# G-PiC_MotorShield.net
KiCad netlist of a schematic drawn in EAGLE
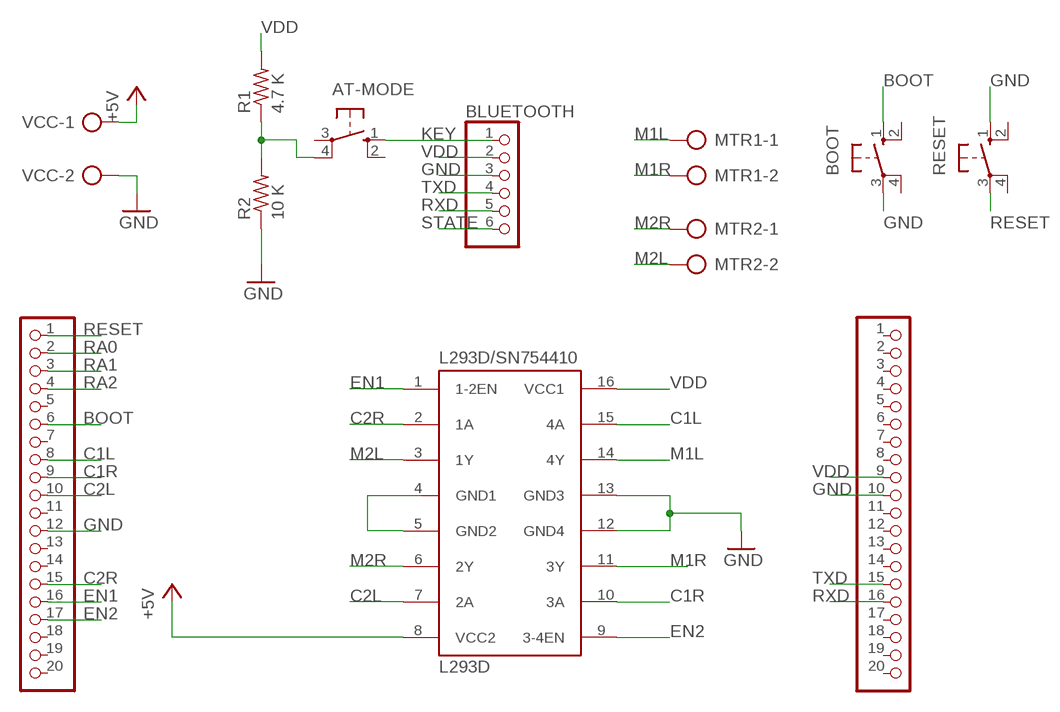
[diagram p0: schematic, sheet 1]

(export (version "E")
  (design (tool "Eeschema 10.0.6"))
  (components
    (comp (ref "AT-MODE")
      (value "10-XX")
      (footprint "eagle-import:B3F-10XX")
      (fields
        (field (name "MPN") "B3F-1000")
        (field (name "MPN_1") "B3F-1000")
        (field (name "OC_FARNELL") "176432")
        (field (name "OC_NEWARK") "36M3542")
      )
      (libsource (lib "eagle-import") (part "10-XX"))
    )
    (comp (ref "BLUETOOTH")
      (value "PINHD-1X6")
      (footprint "eagle-import:1X06")
      (libsource (lib "eagle-import") (part "PINHD-1X6"))
    )
    (comp (ref "BOOT")
      (value "10-XX")
      (footprint "eagle-import:B3F-10XX")
      (fields (field (name "MPN") "B3F-1000"))
      (libsource (lib "eagle-import") (part "10-XX"))
    )
    (comp (ref "JP1")
      (value "PINHD-1X20")
      (footprint "eagle-import:1X20")
      (libsource (lib "eagle-import") (part "PINHD-1X20"))
    )
    (comp (ref "JP2")
      (value "PINHD-1X20")
      (footprint "eagle-import:1X20")
      (libsource (lib "eagle-import") (part "PINHD-1X20"))
    )
    (comp (ref "L293D/SN754410")
      (value "L293D")
      (footprint "eagle-import:DIL16")
      (libsource (lib "eagle-import") (part "L293D"))
    )
    (comp (ref "MTR1")
      (value "AK300/2")
      (footprint "eagle-import:AK300_2")
      (libsource (lib "eagle-import") (part "AK300/2"))
    )
    (comp (ref "MTR2")
      (value "AK300/2")
      (footprint "eagle-import:AK300_2")
      (libsource (lib "eagle-import") (part "AK300/2"))
    )
    (comp (ref "R1")
      (value "4.7 K")
      (footprint "eagle-import:0204_7")
      (libsource (lib "eagle-import") (part "R-US_0204/7"))
    )
    (comp (ref "R2")
      (value "10 K")
      (footprint "eagle-import:0204_7")
      (libsource (lib "eagle-import") (part "R-US_0204/7"))
    )
    (comp (ref "RESET")
      (value "10-XX")
      (footprint "eagle-import:B3F-10XX")
      (fields
        (field (name "MPN") "B3F-1000")
        (field (name "MPN_1") "B3F-1000")
        (field (name "OC_FARNELL") "176432")
        (field (name "OC_NEWARK") "36M3542")
      )
      (libsource (lib "eagle-import") (part "10-XX"))
    )
    (comp (ref "VCC")
      (value "AK300/2")
      (footprint "eagle-import:AK300_2")
      (libsource (lib "eagle-import") (part "AK300/2"))
    )
  )
  (nets
    (net (code "1") (name "+5V") (class "Default")
      (node (ref "L293D/SN754410") (pin "8") (pinfunction "VCC2_8") (pintype "power_in"))
      (node (ref "VCC") (pin "1") (pinfunction "KL_1") (pintype "passive"))
    )
    (net (code "2") (name "/BOOT") (class "Default")
      (node (ref "BOOT") (pin "1") (pinfunction "S_1") (pintype "passive"))
      (node (ref "JP2") (pin "6") (pinfunction "6_6") (pintype "passive"))
    )
    (net (code "3") (name "/C1L") (class "Default")
      (node (ref "JP2") (pin "8") (pinfunction "8_8") (pintype "passive"))
      (node (ref "L293D/SN754410") (pin "15") (pinfunction "4A_15") (pintype "input"))
    )
    (net (code "4") (name "/C1R") (class "Default")
      (node (ref "JP2") (pin "9") (pinfunction "9_9") (pintype "passive"))
      (node (ref "L293D/SN754410") (pin "10") (pinfunction "3A_10") (pintype "input"))
    )
    (net (code "5") (name "/C2L") (class "Default")
      (node (ref "JP2") (pin "10") (pinfunction "10_10") (pintype "passive"))
      (node (ref "L293D/SN754410") (pin "7") (pinfunction "2A_7") (pintype "input"))
    )
    (net (code "6") (name "/C2R") (class "Default")
      (node (ref "JP2") (pin "15") (pinfunction "15_15") (pintype "passive"))
      (node (ref "L293D/SN754410") (pin "2") (pinfunction "1A_2") (pintype "input"))
    )
    (net (code "7") (name "/EN1") (class "Default")
      (node (ref "JP2") (pin "16") (pinfunction "16_16") (pintype "passive"))
      (node (ref "L293D/SN754410") (pin "1") (pinfunction "1-2EN_1") (pintype "input"))
    )
    (net (code "8") (name "/EN2") (class "Default")
      (node (ref "JP2") (pin "17") (pinfunction "17_17") (pintype "passive"))
      (node (ref "L293D/SN754410") (pin "9") (pinfunction "3-4EN_9") (pintype "input"))
    )
    (net (code "9") (name "/KEY") (class "Default")
      (node (ref "AT-MODE") (pin "4") (pinfunction "P1_4") (pintype "passive"))
      (node (ref "R1") (pin "1") (pinfunction "1_1") (pintype "passive"))
      (node (ref "R2") (pin "2") (pinfunction "2_2") (pintype "passive"))
    )
    (net (code "10") (name "/M1L") (class "Default")
      (node (ref "L293D/SN754410") (pin "14") (pinfunction "4Y_14") (pintype "output"))
      (node (ref "MTR1") (pin "1") (pinfunction "KL_1") (pintype "passive"))
    )
    (net (code "11") (name "/M1R") (class "Default")
      (node (ref "L293D/SN754410") (pin "11") (pinfunction "3Y_11") (pintype "output"))
      (node (ref "MTR1") (pin "2") (pinfunction "KL_2") (pintype "passive"))
    )
    (net (code "12") (name "/M2L") (class "Default")
      (node (ref "L293D/SN754410") (pin "3") (pinfunction "1Y_3") (pintype "output"))
      (node (ref "MTR2") (pin "2") (pinfunction "KL_2") (pintype "passive"))
    )
    (net (code "13") (name "/M2R") (class "Default")
      (node (ref "L293D/SN754410") (pin "6") (pinfunction "2Y_6") (pintype "output"))
      (node (ref "MTR2") (pin "1") (pinfunction "KL_1") (pintype "passive"))
    )
    (net (code "14") (name "/RA0") (class "Default")
      (node (ref "JP2") (pin "2") (pinfunction "2_2") (pintype "passive"))
    )
    (net (code "15") (name "/RA1") (class "Default")
      (node (ref "JP2") (pin "3") (pinfunction "3_3") (pintype "passive"))
    )
    (net (code "16") (name "/RA2") (class "Default")
      (node (ref "JP2") (pin "4") (pinfunction "4_4") (pintype "passive"))
    )
    (net (code "17") (name "/RESET") (class "Default")
      (node (ref "JP2") (pin "1") (pinfunction "1_1") (pintype "passive"))
      (node (ref "RESET") (pin "3") (pinfunction "P_3") (pintype "passive"))
    )
    (net (code "18") (name "/RXD") (class "Default")
      (node (ref "BLUETOOTH") (pin "5") (pinfunction "5_5") (pintype "passive"))
      (node (ref "JP1") (pin "16") (pinfunction "16_16") (pintype "passive"))
    )
    (net (code "19") (name "/STATE") (class "Default")
      (node (ref "BLUETOOTH") (pin "6") (pinfunction "6_6") (pintype "passive"))
    )
    (net (code "20") (name "/TXD") (class "Default")
      (node (ref "BLUETOOTH") (pin "4") (pinfunction "4_4") (pintype "passive"))
      (node (ref "JP1") (pin "15") (pinfunction "15_15") (pintype "passive"))
    )
    (net (code "21") (name "/VDD") (class "Default")
      (node (ref "BLUETOOTH") (pin "2") (pinfunction "2_2") (pintype "passive"))
      (node (ref "JP1") (pin "9") (pinfunction "9_9") (pintype "passive"))
      (node (ref "L293D/SN754410") (pin "16") (pinfunction "VCC1_16") (pintype "power_in"))
      (node (ref "R1") (pin "2") (pinfunction "2_2") (pintype "passive"))
    )
    (net (code "22") (name "GND") (class "Default")
      (node (ref "BLUETOOTH") (pin "3") (pinfunction "3_3") (pintype "passive"))
      (node (ref "BOOT") (pin "3") (pinfunction "P_3") (pintype "passive"))
      (node (ref "JP1") (pin "10") (pinfunction "10_10") (pintype "passive"))
      (node (ref "JP2") (pin "12") (pinfunction "12_12") (pintype "passive"))
      (node (ref "L293D/SN754410") (pin "12") (pinfunction "GND4_12") (pintype "power_in"))
      (node (ref "L293D/SN754410") (pin "13") (pinfunction "GND3_13") (pintype "power_in"))
      (node (ref "R2") (pin "1") (pinfunction "1_1") (pintype "passive"))
      (node (ref "RESET") (pin "1") (pinfunction "S_1") (pintype "passive"))
      (node (ref "VCC") (pin "2") (pinfunction "KL_2") (pintype "passive"))
    )
    (net (code "23") (name "Net-(AT-MODE-S)") (class "Default")
      (node (ref "AT-MODE") (pin "1") (pinfunction "S_1") (pintype "passive"))
      (node (ref "BLUETOOTH") (pin "1") (pinfunction "1_1") (pintype "passive"))
    )
    (net (code "24") (name "Net-(L293D/SN754410-GND1)") (class "Default")
      (node (ref "L293D/SN754410") (pin "4") (pinfunction "GND1_4") (pintype "power_in"))
      (node (ref "L293D/SN754410") (pin "5") (pinfunction "GND2_5") (pintype "power_in"))
    )
    (net (code "25") (name "unconnected-(AT-MODE-P-Pad3)") (class "Default")
      (node (ref "AT-MODE") (pin "3") (pinfunction "P_3") (pintype "passive"))
    )
    (net (code "26") (name "unconnected-(AT-MODE-S1-Pad2)") (class "Default")
      (node (ref "AT-MODE") (pin "2") (pinfunction "S1_2") (pintype "passive"))
    )
    (net (code "27") (name "unconnected-(BOOT-P1-Pad4)") (class "Default")
      (node (ref "BOOT") (pin "4") (pinfunction "P1_4") (pintype "passive"))
    )
    (net (code "28") (name "unconnected-(BOOT-S1-Pad2)") (class "Default")
      (node (ref "BOOT") (pin "2") (pinfunction "S1_2") (pintype "passive"))
    )
    (net (code "29") (name "unconnected-(JP1-Pad1)") (class "Default")
      (node (ref "JP1") (pin "1") (pinfunction "1_1") (pintype "passive"))
    )
    (net (code "30") (name "unconnected-(JP1-Pad2)") (class "Default")
      (node (ref "JP1") (pin "2") (pinfunction "2_2") (pintype "passive"))
    )
    (net (code "31") (name "unconnected-(JP1-Pad3)") (class "Default")
      (node (ref "JP1") (pin "3") (pinfunction "3_3") (pintype "passive"))
    )
    (net (code "32") (name "unconnected-(JP1-Pad4)") (class "Default")
      (node (ref "JP1") (pin "4") (pinfunction "4_4") (pintype "passive"))
    )
    (net (code "33") (name "unconnected-(JP1-Pad5)") (class "Default")
      (node (ref "JP1") (pin "5") (pinfunction "5_5") (pintype "passive"))
    )
    (net (code "34") (name "unconnected-(JP1-Pad6)") (class "Default")
      (node (ref "JP1") (pin "6") (pinfunction "6_6") (pintype "passive"))
    )
    (net (code "35") (name "unconnected-(JP1-Pad7)") (class "Default")
      (node (ref "JP1") (pin "7") (pinfunction "7_7") (pintype "passive"))
    )
    (net (code "36") (name "unconnected-(JP1-Pad8)") (class "Default")
      (node (ref "JP1") (pin "8") (pinfunction "8_8") (pintype "passive"))
    )
    (net (code "37") (name "unconnected-(JP1-Pad11)") (class "Default")
      (node (ref "JP1") (pin "11") (pinfunction "11_11") (pintype "passive"))
    )
    (net (code "38") (name "unconnected-(JP1-Pad12)") (class "Default")
      (node (ref "JP1") (pin "12") (pinfunction "12_12") (pintype "passive"))
    )
    (net (code "39") (name "unconnected-(JP1-Pad13)") (class "Default")
      (node (ref "JP1") (pin "13") (pinfunction "13_13") (pintype "passive"))
    )
    (net (code "40") (name "unconnected-(JP1-Pad14)") (class "Default")
      (node (ref "JP1") (pin "14") (pinfunction "14_14") (pintype "passive"))
    )
    (net (code "41") (name "unconnected-(JP1-Pad17)") (class "Default")
      (node (ref "JP1") (pin "17") (pinfunction "17_17") (pintype "passive"))
    )
    (net (code "42") (name "unconnected-(JP1-Pad18)") (class "Default")
      (node (ref "JP1") (pin "18") (pinfunction "18_18") (pintype "passive"))
    )
    (net (code "43") (name "unconnected-(JP1-Pad19)") (class "Default")
      (node (ref "JP1") (pin "19") (pinfunction "19_19") (pintype "passive"))
    )
    (net (code "44") (name "unconnected-(JP1-Pad20)") (class "Default")
      (node (ref "JP1") (pin "20") (pinfunction "20_20") (pintype "passive"))
    )
    (net (code "45") (name "unconnected-(JP2-Pad5)") (class "Default")
      (node (ref "JP2") (pin "5") (pinfunction "5_5") (pintype "passive"))
    )
    (net (code "46") (name "unconnected-(JP2-Pad7)") (class "Default")
      (node (ref "JP2") (pin "7") (pinfunction "7_7") (pintype "passive"))
    )
    (net (code "47") (name "unconnected-(JP2-Pad11)") (class "Default")
      (node (ref "JP2") (pin "11") (pinfunction "11_11") (pintype "passive"))
    )
    (net (code "48") (name "unconnected-(JP2-Pad13)") (class "Default")
      (node (ref "JP2") (pin "13") (pinfunction "13_13") (pintype "passive"))
    )
    (net (code "49") (name "unconnected-(JP2-Pad14)") (class "Default")
      (node (ref "JP2") (pin "14") (pinfunction "14_14") (pintype "passive"))
    )
    (net (code "50") (name "unconnected-(JP2-Pad18)") (class "Default")
      (node (ref "JP2") (pin "18") (pinfunction "18_18") (pintype "passive"))
    )
    (net (code "51") (name "unconnected-(JP2-Pad19)") (class "Default")
      (node (ref "JP2") (pin "19") (pinfunction "19_19") (pintype "passive"))
    )
    (net (code "52") (name "unconnected-(JP2-Pad20)") (class "Default")
      (node (ref "JP2") (pin "20") (pinfunction "20_20") (pintype "passive"))
    )
    (net (code "53") (name "unconnected-(RESET-P1-Pad4)") (class "Default")
      (node (ref "RESET") (pin "4") (pinfunction "P1_4") (pintype "passive"))
    )
    (net (code "54") (name "unconnected-(RESET-S1-Pad2)") (class "Default")
      (node (ref "RESET") (pin "2") (pinfunction "S1_2") (pintype "passive"))
    )
  )
)
